# Sheet3-can.net
KiCad netlist of a schematic drawn in Altium Designer
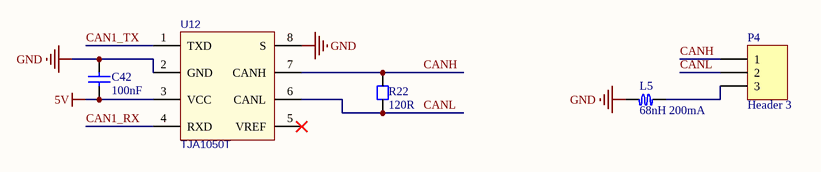
[diagram p0: Sheet3-can.SchDoc]

(export (version "E")
  (design (tool "Eeschema 10.0.6"))
  (components
    (comp (ref "C42")
      (value "100nF")
      (footprint "CC1608-0603")
      (description "0603封装的电容")
      (fields (field (name "PUBLISHER") "Altium Limited"))
      (libsource (lib "base") (part "Cap Chip 0603"))
    )
    (comp (ref "L5")
      (value "68nH 200mA")
      (footprint "Inductor-0603")
      (description "贴片电感 0603封装")
      (libsource (lib "base") (part "Inductor-0603"))
    )
    (comp (ref "P4")
      (value "Header 3")
      (footprint "HX2.54-3")
      (description "Header, 3-Pin")
      (fields (field (name "PUBLISHER") "Altium Limited"))
      (libsource (lib "Connectors") (part "Header 3"))
    )
    (comp (ref "R22")
      (value "120R")
      (footprint "CR1608-0603")
      (description "0603封装电阻")
      (fields (field (name "PUBLISHER") "Altium Limited"))
      (libsource (lib "base") (part "Resistor Chip 0603"))
    )
    (comp (ref "U12")
      (value "TJA1050T")
      (footprint "SOIC-8")
      (description "1Mhz Can芯片，兼容3.3~5V设备")
      (fields
        (field (name "BOM_MANUFACTURER PART") "TJA1050T/CM,118")
        (field (name "BOM_SUPPLIER PART") "C6952")
      )
      (libsource (lib "PB-Chip") (part "TJA1050T"))
    )
  )
  (nets
    (net (code "1") (name "/CAN1_RX") (class "Default")
      (node (ref "U12") (pin "4") (pinfunction "RXD_4") (pintype "passive"))
    )
    (net (code "2") (name "/CAN1_TX") (class "Default")
      (node (ref "U12") (pin "1") (pinfunction "TXD_1") (pintype "passive"))
    )
    (net (code "3") (name "/CANH") (class "Default")
      (node (ref "P4") (pin "1") (pinfunction "1_1") (pintype "passive"))
      (node (ref "R22") (pin "2") (pinfunction "2_2") (pintype "passive"))
      (node (ref "U12") (pin "7") (pinfunction "CANH_7") (pintype "passive"))
    )
    (net (code "4") (name "/CANL") (class "Default")
      (node (ref "P4") (pin "2") (pinfunction "2_2") (pintype "passive"))
      (node (ref "R22") (pin "1") (pinfunction "1_1") (pintype "passive"))
      (node (ref "U12") (pin "6") (pinfunction "CANL_6") (pintype "passive"))
    )
    (net (code "5") (name "5V") (class "Default")
      (node (ref "C42") (pin "1") (pinfunction "1_1") (pintype "passive"))
      (node (ref "U12") (pin "3") (pinfunction "VCC_3") (pintype "passive"))
    )
    (net (code "6") (name "GND") (class "Default")
      (node (ref "C42") (pin "2") (pinfunction "2_2") (pintype "passive"))
      (node (ref "L5") (pin "2") (pinfunction "2_2") (pintype "passive"))
      (node (ref "U12") (pin "2") (pinfunction "GND_2") (pintype "passive"))
      (node (ref "U12") (pin "8") (pinfunction "S_8") (pintype "passive"))
    )
    (net (code "7") (name "Net-(L5-Pad1)") (class "Default")
      (node (ref "L5") (pin "1") (pinfunction "1_1") (pintype "passive"))
      (node (ref "P4") (pin "3") (pinfunction "3_3") (pintype "passive"))
    )
    (net (code "8") (name "unconnected-(U12-VREF-Pad5)") (class "Default")
      (node (ref "U12") (pin "5") (pinfunction "VREF_5") (pintype "passive+no_connect"))
    )
  )
)
